# Schematic.net
KiCad netlist of a schematic drawn in EAGLE
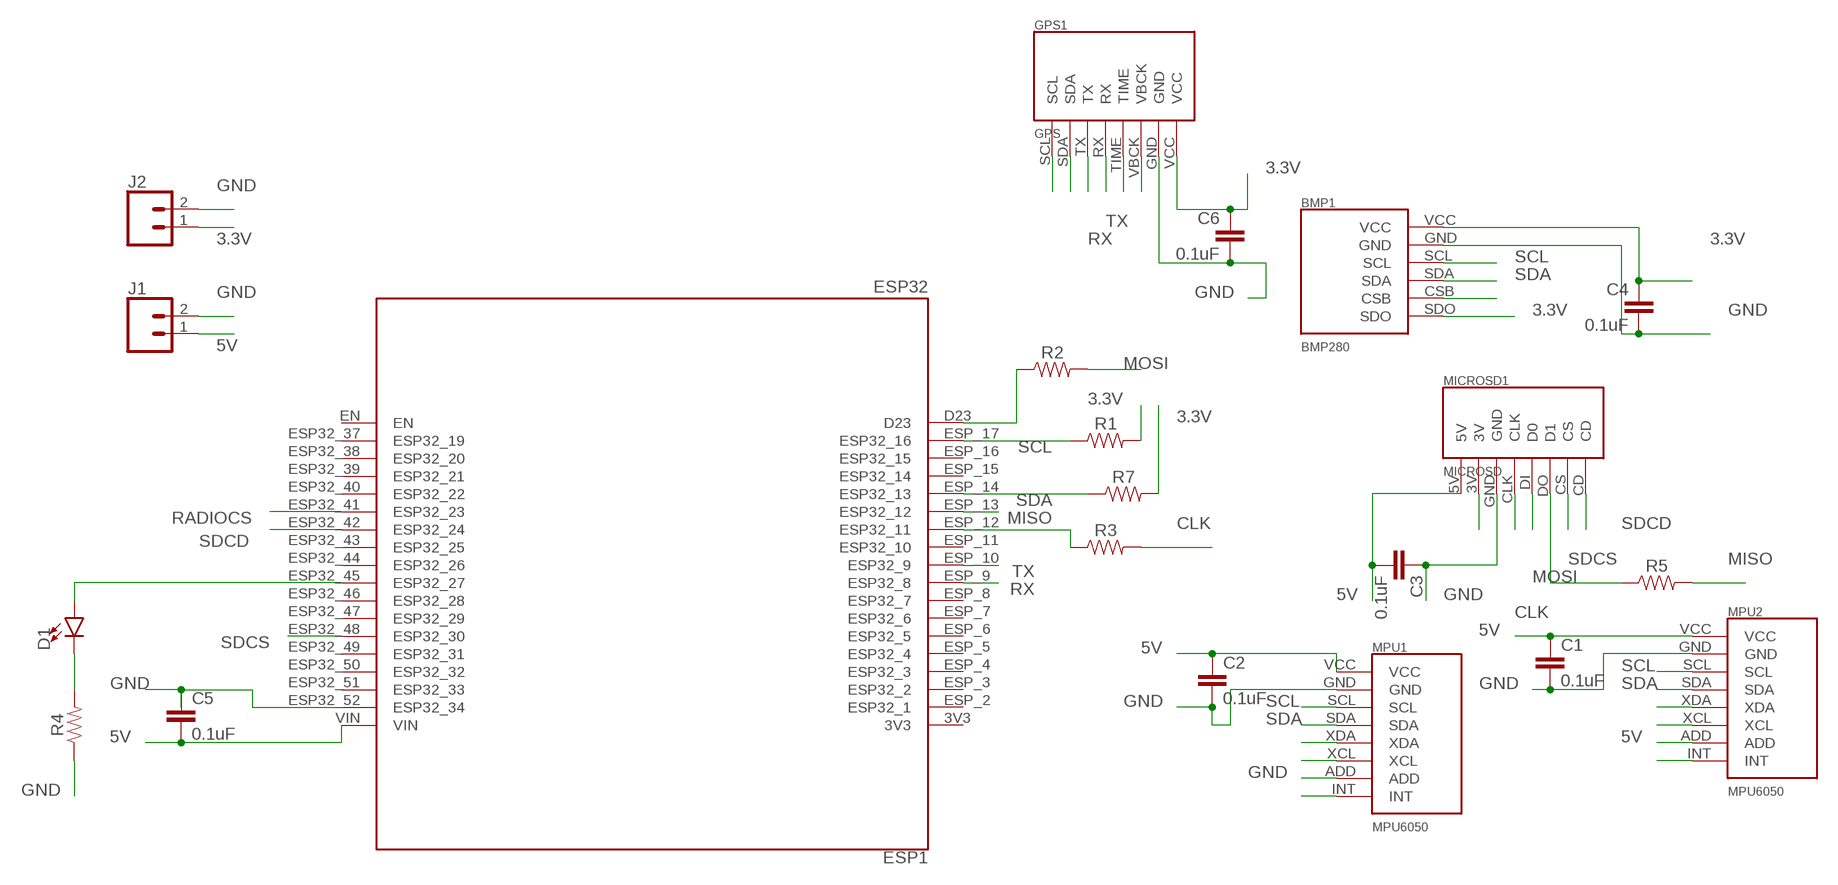
[diagram p0: schematic, sheet 1]

(export (version "E")
  (design (tool "Eeschema 10.0.6"))
  (components
    (comp (ref "BMP1")
      (value "BMP280")
      (footprint "eagle-import:BMP280")
      (libsource (lib "eagle-import") (part "BMP280"))
    )
    (comp (ref "C1")
      (value "0.1uF")
      (footprint "eagle-import:CAP-PTH-SMALL-KIT")
      (libsource (lib "eagle-import") (part "0.1UF-KIT-EZ-50V-20%"))
    )
    (comp (ref "C2")
      (value "0.1uF")
      (footprint "eagle-import:CAP-PTH-SMALL-KIT")
      (libsource (lib "eagle-import") (part "0.1UF-KIT-EZ-50V-20%"))
    )
    (comp (ref "C3")
      (value "0.1uF")
      (footprint "eagle-import:CAP-PTH-SMALL-KIT")
      (libsource (lib "eagle-import") (part "0.1UF-KIT-EZ-50V-20%"))
    )
    (comp (ref "C4")
      (value "0.1uF")
      (footprint "eagle-import:CAP-PTH-SMALL-KIT")
      (libsource (lib "eagle-import") (part "0.1UF-KIT-EZ-50V-20%"))
    )
    (comp (ref "C5")
      (value "0.1uF")
      (footprint "eagle-import:CAP-PTH-SMALL-KIT")
      (libsource (lib "eagle-import") (part "0.1UF-KIT-EZ-50V-20%"))
    )
    (comp (ref "C6")
      (value "0.1uF")
      (footprint "eagle-import:CAP-PTH-SMALL-KIT")
      (libsource (lib "eagle-import") (part "0.1UF-KIT-EZ-50V-20%"))
    )
    (comp (ref "D1")
      (value "LED-3MM-NO_SILK")
      (footprint "eagle-import:LED_3MM-NS")
      (libsource (lib "eagle-import") (part "LED-3MM-NO_SILK"))
    )
    (comp (ref "ESP1")
      (value "ESP32")
      (footprint "eagle-import:ESP32")
      (libsource (lib "eagle-import") (part "ESP32"))
    )
    (comp (ref "GPS1")
      (value "GPS")
      (footprint "eagle-import:GPS")
      (libsource (lib "eagle-import") (part "GPS"))
    )
    (comp (ref "J1")
      (value "CONN_02")
      (footprint "eagle-import:1X02")
      (libsource (lib "eagle-import") (part "CONN_02"))
    )
    (comp (ref "J2")
      (value "CONN_02")
      (footprint "eagle-import:1X02")
      (libsource (lib "eagle-import") (part "CONN_02"))
    )
    (comp (ref "MICROSD1")
      (value "MICROSD")
      (footprint "eagle-import:MICROSD")
      (libsource (lib "eagle-import") (part "MICROSD"))
    )
    (comp (ref "MPU1")
      (value "MPU6050")
      (footprint "eagle-import:MPU6050")
      (libsource (lib "eagle-import") (part "MPU6050"))
    )
    (comp (ref "MPU2")
      (value "MPU6050")
      (footprint "eagle-import:MPU6050")
      (libsource (lib "eagle-import") (part "MPU6050"))
    )
    (comp (ref "R1")
      (value "RESISTORAXIAL-0.3")
      (footprint "eagle-import:AXIAL-0.3")
      (libsource (lib "eagle-import") (part "RESISTORAXIAL-0.3"))
    )
    (comp (ref "R2")
      (value "RESISTORAXIAL-0.3")
      (footprint "eagle-import:AXIAL-0.3")
      (libsource (lib "eagle-import") (part "RESISTORAXIAL-0.3"))
    )
    (comp (ref "R3")
      (value "RESISTORAXIAL-0.3")
      (footprint "eagle-import:AXIAL-0.3")
      (libsource (lib "eagle-import") (part "RESISTORAXIAL-0.3"))
    )
    (comp (ref "R4")
      (value "RESISTORAXIAL-0.3")
      (footprint "eagle-import:AXIAL-0.3")
      (libsource (lib "eagle-import") (part "RESISTORAXIAL-0.3"))
    )
    (comp (ref "R5")
      (value "RESISTORAXIAL-0.3")
      (footprint "eagle-import:AXIAL-0.3")
      (libsource (lib "eagle-import") (part "RESISTORAXIAL-0.3"))
    )
    (comp (ref "R7")
      (value "RESISTORAXIAL-0.3")
      (footprint "eagle-import:AXIAL-0.3")
      (libsource (lib "eagle-import") (part "RESISTORAXIAL-0.3"))
    )
  )
  (nets
    (net (code "1") (name "/3.3V") (class "Default")
      (node (ref "BMP1") (pin "SDO") (pinfunction "SDO_SDO") (pintype "bidirectional"))
      (node (ref "BMP1") (pin "VCC") (pinfunction "VCC_VCC") (pintype "bidirectional"))
      (node (ref "C4") (pin "1") (pinfunction "1_1") (pintype "passive"))
      (node (ref "C6") (pin "1") (pinfunction "1_1") (pintype "passive"))
      (node (ref "GPS1") (pin "VCC") (pinfunction "VCC_VCC") (pintype "bidirectional"))
      (node (ref "J2") (pin "1") (pinfunction "1_1") (pintype "passive"))
      (node (ref "R1") (pin "P$2") (pinfunction "2_P$2") (pintype "passive"))
      (node (ref "R7") (pin "P$2") (pinfunction "2_P$2") (pintype "passive"))
    )
    (net (code "2") (name "/5V") (class "Default")
      (node (ref "C1") (pin "1") (pinfunction "1_1") (pintype "passive"))
      (node (ref "C2") (pin "1") (pinfunction "1_1") (pintype "passive"))
      (node (ref "C3") (pin "2") (pinfunction "2_2") (pintype "passive"))
      (node (ref "C5") (pin "2") (pinfunction "2_2") (pintype "passive"))
      (node (ref "ESP1") (pin "VIN") (pinfunction "VIN_VIN") (pintype "bidirectional"))
      (node (ref "J1") (pin "1") (pinfunction "1_1") (pintype "passive"))
      (node (ref "MICROSD1") (pin "5V") (pinfunction "5V_5V") (pintype "bidirectional"))
      (node (ref "MPU1") (pin "VCC") (pinfunction "VCC_VCC") (pintype "bidirectional"))
      (node (ref "MPU2") (pin "ADD") (pinfunction "ADD_ADD") (pintype "bidirectional"))
      (node (ref "MPU2") (pin "VCC") (pinfunction "VCC_VCC") (pintype "bidirectional"))
    )
    (net (code "3") (name "/CLK") (class "Default")
      (node (ref "MICROSD1") (pin "CLK") (pinfunction "CLK_CLK") (pintype "bidirectional"))
      (node (ref "R3") (pin "P$2") (pinfunction "2_P$2") (pintype "passive"))
    )
    (net (code "4") (name "/GND") (class "Default")
      (node (ref "BMP1") (pin "GND") (pinfunction "GND_GND") (pintype "bidirectional"))
      (node (ref "C1") (pin "2") (pinfunction "2_2") (pintype "passive"))
      (node (ref "C2") (pin "2") (pinfunction "2_2") (pintype "passive"))
      (node (ref "C3") (pin "1") (pinfunction "1_1") (pintype "passive"))
      (node (ref "C4") (pin "2") (pinfunction "2_2") (pintype "passive"))
      (node (ref "C5") (pin "1") (pinfunction "1_1") (pintype "passive"))
      (node (ref "C6") (pin "2") (pinfunction "2_2") (pintype "passive"))
      (node (ref "ESP1") (pin "ESP32_52") (pinfunction "ESP32_34_ESP32_52") (pintype "bidirectional"))
      (node (ref "GPS1") (pin "GND") (pinfunction "GND_GND") (pintype "bidirectional"))
      (node (ref "J1") (pin "2") (pinfunction "2_2") (pintype "passive"))
      (node (ref "J2") (pin "2") (pinfunction "2_2") (pintype "passive"))
      (node (ref "MICROSD1") (pin "GND") (pinfunction "GND_GND") (pintype "bidirectional"))
      (node (ref "MPU1") (pin "ADD") (pinfunction "ADD_ADD") (pintype "bidirectional"))
      (node (ref "MPU1") (pin "GND") (pinfunction "GND_GND") (pintype "bidirectional"))
      (node (ref "MPU2") (pin "GND") (pinfunction "GND_GND") (pintype "bidirectional"))
      (node (ref "R4") (pin "P$1") (pinfunction "1_P$1") (pintype "passive"))
    )
    (net (code "5") (name "/MISO") (class "Default")
      (node (ref "ESP1") (pin "ESP_13") (pinfunction "ESP32_12_ESP_13") (pintype "bidirectional"))
      (node (ref "R5") (pin "P$2") (pinfunction "2_P$2") (pintype "passive"))
    )
    (net (code "6") (name "/MOSI") (class "Default")
      (node (ref "MICROSD1") (pin "DI") (pinfunction "D0_DI") (pintype "bidirectional"))
      (node (ref "R2") (pin "P$2") (pinfunction "2_P$2") (pintype "passive"))
    )
    (net (code "7") (name "/RADIOCS") (class "Default")
      (node (ref "ESP1") (pin "ESP32_41") (pinfunction "ESP32_23_ESP32_41") (pintype "bidirectional"))
    )
    (net (code "8") (name "/RX") (class "Default")
      (node (ref "ESP1") (pin "ESP_9") (pinfunction "ESP32_8_ESP_9") (pintype "bidirectional"))
      (node (ref "GPS1") (pin "TX") (pinfunction "TX_TX") (pintype "bidirectional"))
    )
    (net (code "9") (name "/SCL") (class "Default")
      (node (ref "BMP1") (pin "SCL") (pinfunction "SCL_SCL") (pintype "bidirectional"))
      (node (ref "ESP1") (pin "ESP_17") (pinfunction "ESP32_16_ESP_17") (pintype "bidirectional"))
      (node (ref "MPU1") (pin "SCL") (pinfunction "SCL_SCL") (pintype "bidirectional"))
      (node (ref "MPU2") (pin "SCL") (pinfunction "SCL_SCL") (pintype "bidirectional"))
      (node (ref "R1") (pin "P$1") (pinfunction "1_P$1") (pintype "passive"))
    )
    (net (code "10") (name "/SDA") (class "Default")
      (node (ref "BMP1") (pin "SDA") (pinfunction "SDA_SDA") (pintype "bidirectional"))
      (node (ref "ESP1") (pin "ESP_14") (pinfunction "ESP32_13_ESP_14") (pintype "bidirectional"))
      (node (ref "MPU1") (pin "SDA") (pinfunction "SDA_SDA") (pintype "bidirectional"))
      (node (ref "MPU2") (pin "SDA") (pinfunction "SDA_SDA") (pintype "bidirectional"))
      (node (ref "R7") (pin "P$1") (pinfunction "1_P$1") (pintype "passive"))
    )
    (net (code "11") (name "/SDCD") (class "Default")
      (node (ref "ESP1") (pin "ESP32_42") (pinfunction "ESP32_24_ESP32_42") (pintype "bidirectional"))
      (node (ref "MICROSD1") (pin "CD") (pinfunction "CD_CD") (pintype "bidirectional"))
    )
    (net (code "12") (name "/SDCS") (class "Default")
      (node (ref "ESP1") (pin "ESP32_48") (pinfunction "ESP32_30_ESP32_48") (pintype "bidirectional"))
      (node (ref "MICROSD1") (pin "CS") (pinfunction "CS_CS") (pintype "bidirectional"))
    )
    (net (code "13") (name "/TX") (class "Default")
      (node (ref "ESP1") (pin "ESP_10") (pinfunction "ESP32_9_ESP_10") (pintype "bidirectional"))
      (node (ref "GPS1") (pin "RX") (pinfunction "RX_RX") (pintype "bidirectional"))
    )
    (net (code "14") (name "Net-(D1-C)") (class "Default")
      (node (ref "D1") (pin "K") (pinfunction "C_K") (pintype "passive"))
      (node (ref "R4") (pin "P$2") (pinfunction "2_P$2") (pintype "passive"))
    )
    (net (code "15") (name "Net-(ESP1-ESP32_11)") (class "Default")
      (node (ref "ESP1") (pin "ESP_12") (pinfunction "ESP32_11_ESP_12") (pintype "bidirectional"))
      (node (ref "R3") (pin "P$1") (pinfunction "1_P$1") (pintype "passive"))
    )
    (net (code "16") (name "Net-(ESP1-ESP32_27)") (class "Default")
      (node (ref "D1") (pin "A") (pinfunction "A_A") (pintype "passive"))
      (node (ref "ESP1") (pin "ESP32_45") (pinfunction "ESP32_27_ESP32_45") (pintype "bidirectional"))
    )
    (net (code "17") (name "Net-(MICROSD1-D1)") (class "Default")
      (node (ref "MICROSD1") (pin "DO") (pinfunction "D1_DO") (pintype "bidirectional"))
      (node (ref "R5") (pin "P$1") (pinfunction "1_P$1") (pintype "passive"))
    )
    (net (code "18") (name "Net-(R2-1)") (class "Default")
      (node (ref "ESP1") (pin "D23") (pinfunction "D23_D23") (pintype "bidirectional"))
      (node (ref "R2") (pin "P$1") (pinfunction "1_P$1") (pintype "passive"))
    )
    (net (code "19") (name "unconnected-(BMP1-PadCSB)") (class "Default")
      (node (ref "BMP1") (pin "CSB") (pinfunction "CSB_CSB") (pintype "bidirectional"))
    )
    (net (code "20") (name "unconnected-(ESP1-ESP32_1-PadESP_2)") (class "Default")
      (node (ref "ESP1") (pin "ESP_2") (pinfunction "ESP32_1_ESP_2") (pintype "bidirectional"))
    )
    (net (code "21") (name "unconnected-(ESP1-ESP32_2-PadESP_3)") (class "Default")
      (node (ref "ESP1") (pin "ESP_3") (pinfunction "ESP32_2_ESP_3") (pintype "bidirectional"))
    )
    (net (code "22") (name "unconnected-(ESP1-ESP32_3-PadESP_4)") (class "Default")
      (node (ref "ESP1") (pin "ESP_4") (pinfunction "ESP32_3_ESP_4") (pintype "bidirectional"))
    )
    (net (code "23") (name "unconnected-(ESP1-ESP32_4-PadESP_5)") (class "Default")
      (node (ref "ESP1") (pin "ESP_5") (pinfunction "ESP32_4_ESP_5") (pintype "bidirectional"))
    )
    (net (code "24") (name "unconnected-(ESP1-ESP32_5-PadESP_6)") (class "Default")
      (node (ref "ESP1") (pin "ESP_6") (pinfunction "ESP32_5_ESP_6") (pintype "bidirectional"))
    )
    (net (code "25") (name "unconnected-(ESP1-ESP32_6-PadESP_7)") (class "Default")
      (node (ref "ESP1") (pin "ESP_7") (pinfunction "ESP32_6_ESP_7") (pintype "bidirectional"))
    )
    (net (code "26") (name "unconnected-(ESP1-ESP32_7-PadESP_8)") (class "Default")
      (node (ref "ESP1") (pin "ESP_8") (pinfunction "ESP32_7_ESP_8") (pintype "bidirectional"))
    )
    (net (code "27") (name "unconnected-(ESP1-ESP32_10-PadESP_11)") (class "Default")
      (node (ref "ESP1") (pin "ESP_11") (pinfunction "ESP32_10_ESP_11") (pintype "bidirectional"))
    )
    (net (code "28") (name "unconnected-(ESP1-ESP32_14-PadESP_15)") (class "Default")
      (node (ref "ESP1") (pin "ESP_15") (pinfunction "ESP32_14_ESP_15") (pintype "bidirectional"))
    )
    (net (code "29") (name "unconnected-(ESP1-ESP32_15-PadESP_16)") (class "Default")
      (node (ref "ESP1") (pin "ESP_16") (pinfunction "ESP32_15_ESP_16") (pintype "bidirectional"))
    )
    (net (code "30") (name "unconnected-(ESP1-ESP32_19-PadESP32_37)") (class "Default")
      (node (ref "ESP1") (pin "ESP32_37") (pinfunction "ESP32_19_ESP32_37") (pintype "bidirectional"))
    )
    (net (code "31") (name "unconnected-(ESP1-ESP32_20-PadESP32_38)") (class "Default")
      (node (ref "ESP1") (pin "ESP32_38") (pinfunction "ESP32_20_ESP32_38") (pintype "bidirectional"))
    )
    (net (code "32") (name "unconnected-(ESP1-ESP32_21-PadESP32_39)") (class "Default")
      (node (ref "ESP1") (pin "ESP32_39") (pinfunction "ESP32_21_ESP32_39") (pintype "bidirectional"))
    )
    (net (code "33") (name "unconnected-(ESP1-ESP32_22-PadESP32_40)") (class "Default")
      (node (ref "ESP1") (pin "ESP32_40") (pinfunction "ESP32_22_ESP32_40") (pintype "bidirectional"))
    )
    (net (code "34") (name "unconnected-(ESP1-ESP32_25-PadESP32_43)") (class "Default")
      (node (ref "ESP1") (pin "ESP32_43") (pinfunction "ESP32_25_ESP32_43") (pintype "bidirectional"))
    )
    (net (code "35") (name "unconnected-(ESP1-ESP32_26-PadESP32_44)") (class "Default")
      (node (ref "ESP1") (pin "ESP32_44") (pinfunction "ESP32_26_ESP32_44") (pintype "bidirectional"))
    )
    (net (code "36") (name "unconnected-(ESP1-ESP32_28-PadESP32_46)") (class "Default")
      (node (ref "ESP1") (pin "ESP32_46") (pinfunction "ESP32_28_ESP32_46") (pintype "bidirectional"))
    )
    (net (code "37") (name "unconnected-(ESP1-ESP32_29-PadESP32_47)") (class "Default")
      (node (ref "ESP1") (pin "ESP32_47") (pinfunction "ESP32_29_ESP32_47") (pintype "bidirectional"))
    )
    (net (code "38") (name "unconnected-(ESP1-ESP32_31-PadESP32_49)") (class "Default")
      (node (ref "ESP1") (pin "ESP32_49") (pinfunction "ESP32_31_ESP32_49") (pintype "bidirectional"))
    )
    (net (code "39") (name "unconnected-(ESP1-ESP32_32-PadESP32_50)") (class "Default")
      (node (ref "ESP1") (pin "ESP32_50") (pinfunction "ESP32_32_ESP32_50") (pintype "bidirectional"))
    )
    (net (code "40") (name "unconnected-(ESP1-ESP32_33-PadESP32_51)") (class "Default")
      (node (ref "ESP1") (pin "ESP32_51") (pinfunction "ESP32_33_ESP32_51") (pintype "bidirectional"))
    )
    (net (code "41") (name "unconnected-(ESP1-Pad3V3)") (class "Default")
      (node (ref "ESP1") (pin "3V3") (pinfunction "3V3_3V3") (pintype "bidirectional"))
    )
    (net (code "42") (name "unconnected-(ESP1-PadEN)") (class "Default")
      (node (ref "ESP1") (pin "EN") (pinfunction "EN_EN") (pintype "bidirectional"))
    )
    (net (code "43") (name "unconnected-(GPS1-PadSCL)") (class "Default")
      (node (ref "GPS1") (pin "SCL") (pinfunction "SCL_SCL") (pintype "bidirectional"))
    )
    (net (code "44") (name "unconnected-(GPS1-PadSDA)") (class "Default")
      (node (ref "GPS1") (pin "SDA") (pinfunction "SDA_SDA") (pintype "bidirectional"))
    )
    (net (code "45") (name "unconnected-(GPS1-PadTIME)") (class "Default")
      (node (ref "GPS1") (pin "TIME") (pinfunction "TIME_TIME") (pintype "bidirectional"))
    )
    (net (code "46") (name "unconnected-(GPS1-PadVBCK)") (class "Default")
      (node (ref "GPS1") (pin "VBCK") (pinfunction "VBCK_VBCK") (pintype "bidirectional"))
    )
    (net (code "47") (name "unconnected-(MICROSD1-Pad3V)") (class "Default")
      (node (ref "MICROSD1") (pin "3V") (pinfunction "3V_3V") (pintype "bidirectional"))
    )
    (net (code "48") (name "unconnected-(MPU1-PadINT)") (class "Default")
      (node (ref "MPU1") (pin "INT") (pinfunction "INT_INT") (pintype "bidirectional"))
    )
    (net (code "49") (name "unconnected-(MPU1-PadXCL)") (class "Default")
      (node (ref "MPU1") (pin "XCL") (pinfunction "XCL_XCL") (pintype "bidirectional"))
    )
    (net (code "50") (name "unconnected-(MPU1-PadXDA)") (class "Default")
      (node (ref "MPU1") (pin "XDA") (pinfunction "XDA_XDA") (pintype "bidirectional"))
    )
    (net (code "51") (name "unconnected-(MPU2-PadINT)") (class "Default")
      (node (ref "MPU2") (pin "INT") (pinfunction "INT_INT") (pintype "bidirectional"))
    )
    (net (code "52") (name "unconnected-(MPU2-PadXCL)") (class "Default")
      (node (ref "MPU2") (pin "XCL") (pinfunction "XCL_XCL") (pintype "bidirectional"))
    )
    (net (code "53") (name "unconnected-(MPU2-PadXDA)") (class "Default")
      (node (ref "MPU2") (pin "XDA") (pinfunction "XDA_XDA") (pintype "bidirectional"))
    )
  )
)
